# drill-rev-1.net
KiCad netlist of a schematic drawn in EAGLE
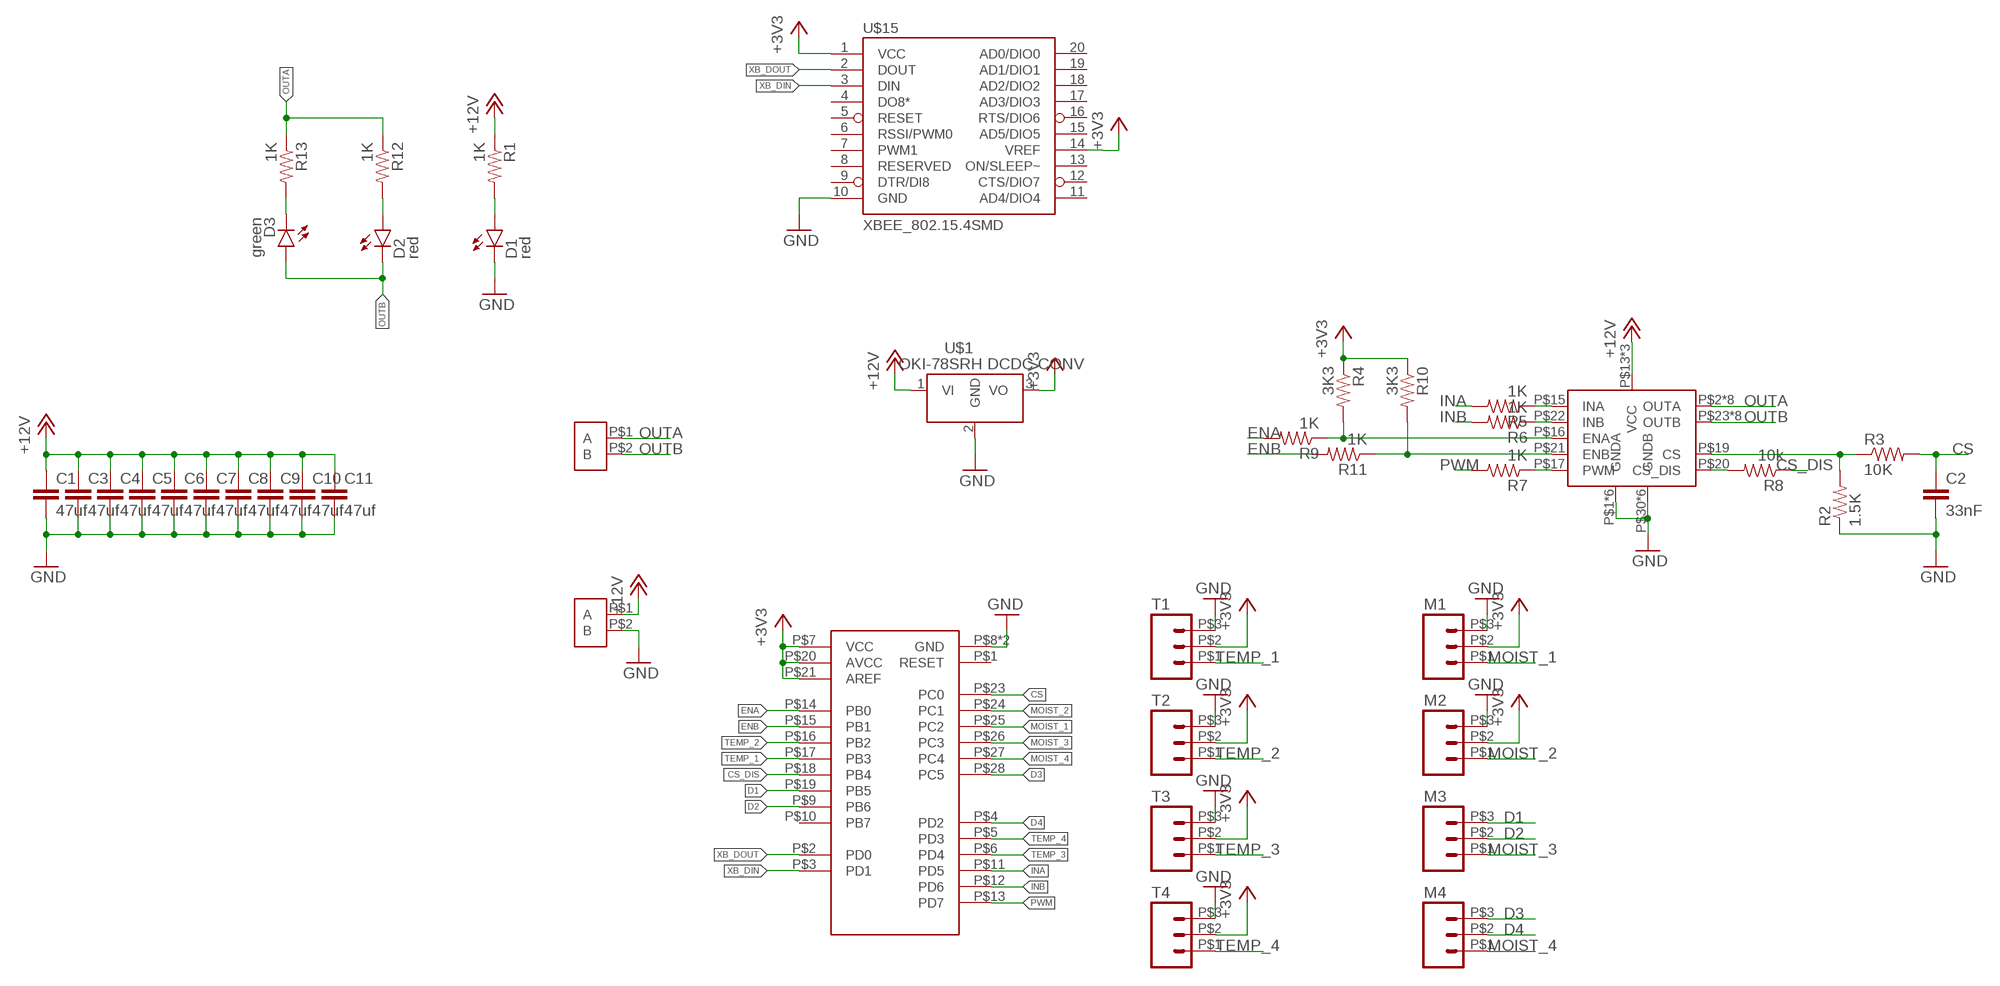
[diagram p0: schematic, sheet 1]

(export (version "E")
  (design (tool "Eeschema 10.0.6"))
  (components
    (comp (ref "C1")
      (value "47uf")
      (footprint "eagle-import:1210")
      (libsource (lib "eagle-import") (part "CAP1210"))
    )
    (comp (ref "C2")
      (value "33nF")
      (footprint "eagle-import:0603-CAP")
      (libsource (lib "eagle-import") (part "CAP0603-CAP"))
    )
    (comp (ref "C3")
      (value "47uf")
      (footprint "eagle-import:1210")
      (libsource (lib "eagle-import") (part "CAP1210"))
    )
    (comp (ref "C4")
      (value "47uf")
      (footprint "eagle-import:1210")
      (libsource (lib "eagle-import") (part "CAP1210"))
    )
    (comp (ref "C5")
      (value "47uf")
      (footprint "eagle-import:1210")
      (libsource (lib "eagle-import") (part "CAP1210"))
    )
    (comp (ref "C6")
      (value "47uf")
      (footprint "eagle-import:1210")
      (libsource (lib "eagle-import") (part "CAP1210"))
    )
    (comp (ref "C7")
      (value "47uf")
      (footprint "eagle-import:1210")
      (libsource (lib "eagle-import") (part "CAP1210"))
    )
    (comp (ref "C8")
      (value "47uf")
      (footprint "eagle-import:1210")
      (libsource (lib "eagle-import") (part "CAP1210"))
    )
    (comp (ref "C9")
      (value "47uf")
      (footprint "eagle-import:1210")
      (libsource (lib "eagle-import") (part "CAP1210"))
    )
    (comp (ref "C10")
      (value "47uf")
      (footprint "eagle-import:1210")
      (libsource (lib "eagle-import") (part "CAP1210"))
    )
    (comp (ref "C11")
      (value "47uf")
      (footprint "eagle-import:1210")
      (libsource (lib "eagle-import") (part "CAP1210"))
    )
    (comp (ref "D1")
      (value "red")
      (footprint "eagle-import:LED-0603")
      (libsource (lib "eagle-import") (part "LED0603"))
    )
    (comp (ref "D2")
      (value "red")
      (footprint "eagle-import:LED-0603")
      (libsource (lib "eagle-import") (part "LED0603"))
    )
    (comp (ref "D3")
      (value "green")
      (footprint "eagle-import:LED-0603")
      (libsource (lib "eagle-import") (part "LED0603"))
    )
    (comp (ref "M1")
      (value "M03VERT")
      (footprint "eagle-import:MOLEX0436500328")
      (libsource (lib "eagle-import") (part "M03VERT"))
    )
    (comp (ref "M2")
      (value "M03VERT")
      (footprint "eagle-import:MOLEX0436500328")
      (libsource (lib "eagle-import") (part "M03VERT"))
    )
    (comp (ref "M3")
      (value "M03VERT")
      (footprint "eagle-import:MOLEX0436500328")
      (libsource (lib "eagle-import") (part "M03VERT"))
    )
    (comp (ref "M4")
      (value "M03VERT")
      (footprint "eagle-import:MOLEX0436500328")
      (libsource (lib "eagle-import") (part "M03VERT"))
    )
    (comp (ref "R1")
      (value "1K")
      (footprint "eagle-import:0603-RES")
      (libsource (lib "eagle-import") (part "RESISTOR0603"))
    )
    (comp (ref "R2")
      (value "1.5K")
      (footprint "eagle-import:0603-RES")
      (libsource (lib "eagle-import") (part "RESISTOR0603"))
    )
    (comp (ref "R3")
      (value "10K")
      (footprint "eagle-import:0603-RES")
      (libsource (lib "eagle-import") (part "RESISTOR0603"))
    )
    (comp (ref "R4")
      (value "3K3")
      (footprint "eagle-import:0603-RES")
      (libsource (lib "eagle-import") (part "RESISTOR0603"))
    )
    (comp (ref "R5")
      (value "1K")
      (footprint "eagle-import:0603-RES")
      (libsource (lib "eagle-import") (part "RESISTOR0603"))
    )
    (comp (ref "R6")
      (value "1K")
      (footprint "eagle-import:0603-RES")
      (libsource (lib "eagle-import") (part "RESISTOR0603"))
    )
    (comp (ref "R7")
      (value "1K")
      (footprint "eagle-import:0603-RES")
      (libsource (lib "eagle-import") (part "RESISTOR0603"))
    )
    (comp (ref "R8")
      (value "10k")
      (footprint "eagle-import:0603-RES")
      (libsource (lib "eagle-import") (part "RESISTOR0603"))
    )
    (comp (ref "R9")
      (value "1K")
      (footprint "eagle-import:0603-RES")
      (libsource (lib "eagle-import") (part "RESISTOR0603"))
    )
    (comp (ref "R10")
      (value "3K3")
      (footprint "eagle-import:0603-RES")
      (libsource (lib "eagle-import") (part "RESISTOR0603"))
    )
    (comp (ref "R11")
      (value "1K")
      (footprint "eagle-import:0603-RES")
      (libsource (lib "eagle-import") (part "RESISTOR0603"))
    )
    (comp (ref "R12")
      (value "1K")
      (footprint "eagle-import:0603-RES")
      (libsource (lib "eagle-import") (part "RESISTOR0603"))
    )
    (comp (ref "R13")
      (value "1K")
      (footprint "eagle-import:0603-RES")
      (libsource (lib "eagle-import") (part "RESISTOR0603"))
    )
    (comp (ref "T1")
      (value "M03VERT")
      (footprint "eagle-import:MOLEX0436500328")
      (libsource (lib "eagle-import") (part "M03VERT"))
    )
    (comp (ref "T2")
      (value "M03VERT")
      (footprint "eagle-import:MOLEX0436500328")
      (libsource (lib "eagle-import") (part "M03VERT"))
    )
    (comp (ref "T3")
      (value "M03VERT")
      (footprint "eagle-import:MOLEX0436500328")
      (libsource (lib "eagle-import") (part "M03VERT"))
    )
    (comp (ref "T4")
      (value "M03VERT")
      (footprint "eagle-import:MOLEX0436500328")
      (libsource (lib "eagle-import") (part "M03VERT"))
    )
    (comp (ref "U$1")
      (value "Q_OKI-78SR")
      (footprint "eagle-import:OKI-78SR_HORIZ")
      (libsource (lib "eagle-import") (part "Q_OKI-78SR"))
    )
    (comp (ref "U$3")
      (value "TE_2POS-5MM_SCREW_TERM")
      (footprint "eagle-import:TE_2POS-5MM_SCREW_TERM")
      (libsource (lib "eagle-import") (part "TE_2POS-5MM_SCREW_TERM"))
    )
    (comp (ref "U$5")
      (value "TE_2POS-5MM_SCREW_TERM")
      (footprint "eagle-import:TE_2POS-5MM_SCREW_TERM")
      (libsource (lib "eagle-import") (part "TE_2POS-5MM_SCREW_TERM"))
    )
    (comp (ref "U$6")
      (value "VNH5XXX_HBRIDGEVNH5050A")
      (footprint "eagle-import:POWERSSO-36_TP")
      (libsource (lib "eagle-import") (part "VNH5XXX_HBRIDGEVNH5050A"))
    )
    (comp (ref "U$13")
      (value "DIP_SKT_ATMEGA")
      (footprint "eagle-import:DIP_SKT_ATMEGA")
      (libsource (lib "eagle-import") (part "DIP_SKT_ATMEGA"))
    )
    (comp (ref "U$15")
      (value "XBEE_802.15.4SMD")
      (footprint "eagle-import:XBEE_802.15.4_SMD")
      (libsource (lib "eagle-import") (part "XBEE_802.15.4SMD"))
    )
  )
  (nets
    (net (code "1") (name "+3V3") (class "Default")
      (node (ref "M1") (pin "P$2") (pinfunction "2_P$2") (pintype "passive"))
      (node (ref "M2") (pin "P$2") (pinfunction "2_P$2") (pintype "passive"))
      (node (ref "R10") (pin "1") (pinfunction "1_1") (pintype "passive"))
      (node (ref "R4") (pin "1") (pinfunction "1_1") (pintype "passive"))
      (node (ref "T1") (pin "P$2") (pinfunction "2_P$2") (pintype "passive"))
      (node (ref "T2") (pin "P$2") (pinfunction "2_P$2") (pintype "passive"))
      (node (ref "T3") (pin "P$2") (pinfunction "2_P$2") (pintype "passive"))
      (node (ref "T4") (pin "P$2") (pinfunction "2_P$2") (pintype "passive"))
      (node (ref "U$1") (pin "3") (pinfunction "VO_3") (pintype "bidirectional"))
      (node (ref "U$13") (pin "P$20") (pinfunction "AVCC_P$20") (pintype "bidirectional"))
      (node (ref "U$13") (pin "P$21") (pinfunction "AREF_P$21") (pintype "bidirectional"))
      (node (ref "U$13") (pin "P$7") (pinfunction "VCC_P$7") (pintype "bidirectional"))
      (node (ref "U$15") (pin "1") (pinfunction "VCC_1") (pintype "power_in"))
      (node (ref "U$15") (pin "14") (pinfunction "VREF_14") (pintype "bidirectional"))
    )
    (net (code "2") (name "+12V") (class "Default")
      (node (ref "C1") (pin "1") (pinfunction "1_1") (pintype "passive"))
      (node (ref "C10") (pin "1") (pinfunction "1_1") (pintype "passive"))
      (node (ref "C11") (pin "1") (pinfunction "1_1") (pintype "passive"))
      (node (ref "C3") (pin "1") (pinfunction "1_1") (pintype "passive"))
      (node (ref "C4") (pin "1") (pinfunction "1_1") (pintype "passive"))
      (node (ref "C5") (pin "1") (pinfunction "1_1") (pintype "passive"))
      (node (ref "C6") (pin "1") (pinfunction "1_1") (pintype "passive"))
      (node (ref "C7") (pin "1") (pinfunction "1_1") (pintype "passive"))
      (node (ref "C8") (pin "1") (pinfunction "1_1") (pintype "passive"))
      (node (ref "C9") (pin "1") (pinfunction "1_1") (pintype "passive"))
      (node (ref "R1") (pin "1") (pinfunction "1_1") (pintype "passive"))
      (node (ref "U$1") (pin "1") (pinfunction "VI_1") (pintype "bidirectional"))
      (node (ref "U$5") (pin "P$1") (pinfunction "A_P$1") (pintype "bidirectional"))
      (node (ref "U$6") (pin "P$13") (pinfunction "VCC_P$13") (pintype "bidirectional"))
      (node (ref "U$6") (pin "P$24") (pinfunction "VCC_P$24") (pintype "bidirectional"))
      (node (ref "U$6") (pin "SLUG1") (pinfunction "VCC_SLUG1") (pintype "bidirectional"))
    )
    (net (code "3") (name "CS") (class "Default")
      (node (ref "C2") (pin "1") (pinfunction "1_1") (pintype "passive"))
      (node (ref "R3") (pin "2") (pinfunction "2_2") (pintype "passive"))
      (node (ref "U$13") (pin "P$23") (pinfunction "PC0_P$23") (pintype "bidirectional"))
    )
    (net (code "4") (name "CS_DIS") (class "Default")
      (node (ref "R8") (pin "1") (pinfunction "1_1") (pintype "passive"))
      (node (ref "U$13") (pin "P$18") (pinfunction "PB4_P$18") (pintype "bidirectional"))
    )
    (net (code "5") (name "D1") (class "Default")
      (node (ref "M3") (pin "P$3") (pinfunction "3_P$3") (pintype "passive"))
      (node (ref "U$13") (pin "P$19") (pinfunction "PB5_P$19") (pintype "bidirectional"))
    )
    (net (code "6") (name "D2") (class "Default")
      (node (ref "M3") (pin "P$2") (pinfunction "2_P$2") (pintype "passive"))
      (node (ref "U$13") (pin "P$9") (pinfunction "PB6_P$9") (pintype "bidirectional"))
    )
    (net (code "7") (name "D3") (class "Default")
      (node (ref "M4") (pin "P$3") (pinfunction "3_P$3") (pintype "passive"))
      (node (ref "U$13") (pin "P$28") (pinfunction "PC5_P$28") (pintype "bidirectional"))
    )
    (net (code "8") (name "D4") (class "Default")
      (node (ref "M4") (pin "P$2") (pinfunction "2_P$2") (pintype "passive"))
      (node (ref "U$13") (pin "P$4") (pinfunction "PD2_P$4") (pintype "bidirectional"))
    )
    (net (code "9") (name "ENA") (class "Default")
      (node (ref "R9") (pin "2") (pinfunction "2_2") (pintype "passive"))
      (node (ref "U$13") (pin "P$14") (pinfunction "PB0_P$14") (pintype "bidirectional"))
    )
    (net (code "10") (name "ENB") (class "Default")
      (node (ref "R11") (pin "2") (pinfunction "2_2") (pintype "passive"))
      (node (ref "U$13") (pin "P$15") (pinfunction "PB1_P$15") (pintype "bidirectional"))
    )
    (net (code "11") (name "GND") (class "Default")
      (node (ref "C1") (pin "2") (pinfunction "2_2") (pintype "passive"))
      (node (ref "C10") (pin "2") (pinfunction "2_2") (pintype "passive"))
      (node (ref "C11") (pin "2") (pinfunction "2_2") (pintype "passive"))
      (node (ref "C2") (pin "2") (pinfunction "2_2") (pintype "passive"))
      (node (ref "C3") (pin "2") (pinfunction "2_2") (pintype "passive"))
      (node (ref "C4") (pin "2") (pinfunction "2_2") (pintype "passive"))
      (node (ref "C5") (pin "2") (pinfunction "2_2") (pintype "passive"))
      (node (ref "C6") (pin "2") (pinfunction "2_2") (pintype "passive"))
      (node (ref "C7") (pin "2") (pinfunction "2_2") (pintype "passive"))
      (node (ref "C8") (pin "2") (pinfunction "2_2") (pintype "passive"))
      (node (ref "C9") (pin "2") (pinfunction "2_2") (pintype "passive"))
      (node (ref "D1") (pin "C") (pinfunction "C_C") (pintype "passive"))
      (node (ref "M1") (pin "P$3") (pinfunction "3_P$3") (pintype "passive"))
      (node (ref "M2") (pin "P$3") (pinfunction "3_P$3") (pintype "passive"))
      (node (ref "R2") (pin "1") (pinfunction "1_1") (pintype "passive"))
      (node (ref "T1") (pin "P$3") (pinfunction "3_P$3") (pintype "passive"))
      (node (ref "T2") (pin "P$3") (pinfunction "3_P$3") (pintype "passive"))
      (node (ref "T3") (pin "P$3") (pinfunction "3_P$3") (pintype "passive"))
      (node (ref "T4") (pin "P$3") (pinfunction "3_P$3") (pintype "passive"))
      (node (ref "U$1") (pin "2") (pinfunction "GND_2") (pintype "bidirectional"))
      (node (ref "U$13") (pin "P$22") (pinfunction "GND_P$22") (pintype "bidirectional"))
      (node (ref "U$13") (pin "P$8") (pinfunction "GND_P$8") (pintype "bidirectional"))
      (node (ref "U$15") (pin "10") (pinfunction "GND_10") (pintype "power_in"))
      (node (ref "U$5") (pin "P$2") (pinfunction "B_P$2") (pintype "bidirectional"))
      (node (ref "U$6") (pin "P$1") (pinfunction "GNDA_P$1") (pintype "bidirectional"))
      (node (ref "U$6") (pin "P$3") (pinfunction "GNDA_P$3") (pintype "bidirectional"))
      (node (ref "U$6") (pin "P$30") (pinfunction "GNDB_P$30") (pintype "bidirectional"))
      (node (ref "U$6") (pin "P$31") (pinfunction "GNDB_P$31") (pintype "bidirectional"))
      (node (ref "U$6") (pin "P$32") (pinfunction "GNDB_P$32") (pintype "bidirectional"))
      (node (ref "U$6") (pin "P$33") (pinfunction "GNDB_P$33") (pintype "bidirectional"))
      (node (ref "U$6") (pin "P$34") (pinfunction "GNDB_P$34") (pintype "bidirectional"))
      (node (ref "U$6") (pin "P$36") (pinfunction "GNDB_P$36") (pintype "bidirectional"))
      (node (ref "U$6") (pin "P$4") (pinfunction "GNDA_P$4") (pintype "bidirectional"))
      (node (ref "U$6") (pin "P$5") (pinfunction "GNDA_P$5") (pintype "bidirectional"))
      (node (ref "U$6") (pin "P$6") (pinfunction "GNDA_P$6") (pintype "bidirectional"))
      (node (ref "U$6") (pin "P$7") (pinfunction "GNDA_P$7") (pintype "bidirectional"))
    )
    (net (code "12") (name "INA") (class "Default")
      (node (ref "R5") (pin "2") (pinfunction "2_2") (pintype "passive"))
      (node (ref "U$13") (pin "P$11") (pinfunction "PD5_P$11") (pintype "bidirectional"))
    )
    (net (code "13") (name "INB") (class "Default")
      (node (ref "R6") (pin "2") (pinfunction "2_2") (pintype "passive"))
      (node (ref "U$13") (pin "P$12") (pinfunction "PD6_P$12") (pintype "bidirectional"))
    )
    (net (code "14") (name "MOIST_1") (class "Default")
      (node (ref "M1") (pin "P$1") (pinfunction "1_P$1") (pintype "passive"))
      (node (ref "U$13") (pin "P$25") (pinfunction "PC2_P$25") (pintype "bidirectional"))
    )
    (net (code "15") (name "MOIST_2") (class "Default")
      (node (ref "M2") (pin "P$1") (pinfunction "1_P$1") (pintype "passive"))
      (node (ref "U$13") (pin "P$24") (pinfunction "PC1_P$24") (pintype "bidirectional"))
    )
    (net (code "16") (name "MOIST_3") (class "Default")
      (node (ref "M3") (pin "P$1") (pinfunction "1_P$1") (pintype "passive"))
      (node (ref "U$13") (pin "P$26") (pinfunction "PC3_P$26") (pintype "bidirectional"))
    )
    (net (code "17") (name "MOIST_4") (class "Default")
      (node (ref "M4") (pin "P$1") (pinfunction "1_P$1") (pintype "passive"))
      (node (ref "U$13") (pin "P$27") (pinfunction "PC4_P$27") (pintype "bidirectional"))
    )
    (net (code "18") (name "Net-(D1-PadA)") (class "Default")
      (node (ref "D1") (pin "A") (pinfunction "A_A") (pintype "passive"))
      (node (ref "R1") (pin "2") (pinfunction "2_2") (pintype "passive"))
    )
    (net (code "19") (name "Net-(D2-PadA)") (class "Default")
      (node (ref "D2") (pin "A") (pinfunction "A_A") (pintype "passive"))
      (node (ref "R12") (pin "2") (pinfunction "2_2") (pintype "passive"))
    )
    (net (code "20") (name "Net-(D3-PadC)") (class "Default")
      (node (ref "D3") (pin "C") (pinfunction "C_C") (pintype "passive"))
      (node (ref "R13") (pin "2") (pinfunction "2_2") (pintype "passive"))
    )
    (net (code "21") (name "Net-(U$6-CS)") (class "Default")
      (node (ref "R2") (pin "2") (pinfunction "2_2") (pintype "passive"))
      (node (ref "R3") (pin "1") (pinfunction "1_1") (pintype "passive"))
      (node (ref "U$6") (pin "P$19") (pinfunction "CS_P$19") (pintype "bidirectional"))
    )
    (net (code "22") (name "Net-(U$6-CS_DIS)") (class "Default")
      (node (ref "R8") (pin "2") (pinfunction "2_2") (pintype "passive"))
      (node (ref "U$6") (pin "P$20") (pinfunction "CS_DIS_P$20") (pintype "bidirectional"))
    )
    (net (code "23") (name "Net-(U$6-ENA)") (class "Default")
      (node (ref "R4") (pin "2") (pinfunction "2_2") (pintype "passive"))
      (node (ref "R9") (pin "1") (pinfunction "1_1") (pintype "passive"))
      (node (ref "U$6") (pin "P$16") (pinfunction "ENA_P$16") (pintype "bidirectional"))
    )
    (net (code "24") (name "Net-(U$6-ENB)") (class "Default")
      (node (ref "R10") (pin "2") (pinfunction "2_2") (pintype "passive"))
      (node (ref "R11") (pin "1") (pinfunction "1_1") (pintype "passive"))
      (node (ref "U$6") (pin "P$21") (pinfunction "ENB_P$21") (pintype "bidirectional"))
    )
    (net (code "25") (name "Net-(U$6-INA)") (class "Default")
      (node (ref "R5") (pin "1") (pinfunction "1_1") (pintype "passive"))
      (node (ref "U$6") (pin "P$15") (pinfunction "INA_P$15") (pintype "bidirectional"))
    )
    (net (code "26") (name "Net-(U$6-INB)") (class "Default")
      (node (ref "R6") (pin "1") (pinfunction "1_1") (pintype "passive"))
      (node (ref "U$6") (pin "P$22") (pinfunction "INB_P$22") (pintype "bidirectional"))
    )
    (net (code "27") (name "Net-(U$6-PWM)") (class "Default")
      (node (ref "R7") (pin "1") (pinfunction "1_1") (pintype "passive"))
      (node (ref "U$6") (pin "P$17") (pinfunction "PWM_P$17") (pintype "bidirectional"))
    )
    (net (code "28") (name "OUTA") (class "Default")
      (node (ref "R12") (pin "1") (pinfunction "1_1") (pintype "passive"))
      (node (ref "R13") (pin "1") (pinfunction "1_1") (pintype "passive"))
      (node (ref "U$3") (pin "P$1") (pinfunction "A_P$1") (pintype "bidirectional"))
      (node (ref "U$6") (pin "P$10") (pinfunction "OUTA_P$10") (pintype "bidirectional"))
      (node (ref "U$6") (pin "P$11") (pinfunction "OUTA_P$11") (pintype "bidirectional"))
      (node (ref "U$6") (pin "P$12") (pinfunction "OUTA_P$12") (pintype "bidirectional"))
      (node (ref "U$6") (pin "P$14") (pinfunction "OUTA_P$14") (pintype "bidirectional"))
      (node (ref "U$6") (pin "P$2") (pinfunction "OUTA_P$2") (pintype "bidirectional"))
      (node (ref "U$6") (pin "P$8") (pinfunction "OUTA_P$8") (pintype "bidirectional"))
      (node (ref "U$6") (pin "P$9") (pinfunction "OUTA_P$9") (pintype "bidirectional"))
      (node (ref "U$6") (pin "SLUG2") (pinfunction "OUTA_SLUG2") (pintype "bidirectional"))
    )
    (net (code "29") (name "OUTB") (class "Default")
      (node (ref "D2") (pin "C") (pinfunction "C_C") (pintype "passive"))
      (node (ref "D3") (pin "A") (pinfunction "A_A") (pintype "passive"))
      (node (ref "U$3") (pin "P$2") (pinfunction "B_P$2") (pintype "bidirectional"))
      (node (ref "U$6") (pin "P$23") (pinfunction "OUTB_P$23") (pintype "bidirectional"))
      (node (ref "U$6") (pin "P$25") (pinfunction "OUTB_P$25") (pintype "bidirectional"))
      (node (ref "U$6") (pin "P$26") (pinfunction "OUTB_P$26") (pintype "bidirectional"))
      (node (ref "U$6") (pin "P$27") (pinfunction "OUTB_P$27") (pintype "bidirectional"))
      (node (ref "U$6") (pin "P$28") (pinfunction "OUTB_P$28") (pintype "bidirectional"))
      (node (ref "U$6") (pin "P$29") (pinfunction "OUTB_P$29") (pintype "bidirectional"))
      (node (ref "U$6") (pin "P$35") (pinfunction "OUTB_P$35") (pintype "bidirectional"))
      (node (ref "U$6") (pin "SLUG3") (pinfunction "OUTB_SLUG3") (pintype "bidirectional"))
    )
    (net (code "30") (name "PWM") (class "Default")
      (node (ref "R7") (pin "2") (pinfunction "2_2") (pintype "passive"))
      (node (ref "U$13") (pin "P$13") (pinfunction "PD7_P$13") (pintype "bidirectional"))
    )
    (net (code "31") (name "TEMP_1") (class "Default")
      (node (ref "T1") (pin "P$1") (pinfunction "1_P$1") (pintype "passive"))
      (node (ref "U$13") (pin "P$17") (pinfunction "PB3_P$17") (pintype "bidirectional"))
    )
    (net (code "32") (name "TEMP_2") (class "Default")
      (node (ref "T2") (pin "P$1") (pinfunction "1_P$1") (pintype "passive"))
      (node (ref "U$13") (pin "P$16") (pinfunction "PB2_P$16") (pintype "bidirectional"))
    )
    (net (code "33") (name "TEMP_3") (class "Default")
      (node (ref "T3") (pin "P$1") (pinfunction "1_P$1") (pintype "passive"))
      (node (ref "U$13") (pin "P$6") (pinfunction "PD4_P$6") (pintype "bidirectional"))
    )
    (net (code "34") (name "TEMP_4") (class "Default")
      (node (ref "T4") (pin "P$1") (pinfunction "1_P$1") (pintype "passive"))
      (node (ref "U$13") (pin "P$5") (pinfunction "PD3_P$5") (pintype "bidirectional"))
    )
    (net (code "35") (name "XB_DIN") (class "Default")
      (node (ref "U$13") (pin "P$3") (pinfunction "PD1_P$3") (pintype "bidirectional"))
      (node (ref "U$15") (pin "3") (pinfunction "DIN_3") (pintype "input"))
    )
    (net (code "36") (name "XB_DOUT") (class "Default")
      (node (ref "U$13") (pin "P$2") (pinfunction "PD0_P$2") (pintype "bidirectional"))
      (node (ref "U$15") (pin "2") (pinfunction "DOUT_2") (pintype "output"))
    )
    (net (code "37") (name "unconnected-(U$13-PB7-PadP$10)") (class "Default")
      (node (ref "U$13") (pin "P$10") (pinfunction "PB7_P$10") (pintype "bidirectional"))
    )
    (net (code "38") (name "unconnected-(U$13-RESET-PadP$1)") (class "Default")
      (node (ref "U$13") (pin "P$1") (pinfunction "RESET_P$1") (pintype "bidirectional"))
    )
    (net (code "39") (name "unconnected-(U$15-AD0{slash}DIO0-Pad20)") (class "Default")
      (node (ref "U$15") (pin "20") (pinfunction "AD0/DIO0_20") (pintype "bidirectional"))
    )
    (net (code "40") (name "unconnected-(U$15-AD1{slash}DIO1-Pad19)") (class "Default")
      (node (ref "U$15") (pin "19") (pinfunction "AD1/DIO1_19") (pintype "bidirectional"))
    )
    (net (code "41") (name "unconnected-(U$15-AD2{slash}DIO2-Pad18)") (class "Default")
      (node (ref "U$15") (pin "18") (pinfunction "AD2/DIO2_18") (pintype "bidirectional"))
    )
    (net (code "42") (name "unconnected-(U$15-AD3{slash}DIO3-Pad17)") (class "Default")
      (node (ref "U$15") (pin "17") (pinfunction "AD3/DIO3_17") (pintype "bidirectional"))
    )
    (net (code "43") (name "unconnected-(U$15-AD4{slash}DIO4-Pad11)") (class "Default")
      (node (ref "U$15") (pin "11") (pinfunction "AD4/DIO4_11") (pintype "bidirectional"))
    )
    (net (code "44") (name "unconnected-(U$15-AD5{slash}DIO5-Pad15)") (class "Default")
      (node (ref "U$15") (pin "15") (pinfunction "AD5/DIO5_15") (pintype "bidirectional"))
    )
    (net (code "45") (name "unconnected-(U$15-CTS{slash}DIO7-Pad12)") (class "Default")
      (node (ref "U$15") (pin "12") (pinfunction "CTS/DIO7_12") (pintype "output"))
    )
    (net (code "46") (name "unconnected-(U$15-DO8*-Pad4)") (class "Default")
      (node (ref "U$15") (pin "4") (pinfunction "DO8*_4") (pintype "bidirectional"))
    )
    (net (code "47") (name "unconnected-(U$15-DTR{slash}DI8-Pad9)") (class "Default")
      (node (ref "U$15") (pin "9") (pinfunction "DTR/DI8_9") (pintype "bidirectional"))
    )
    (net (code "48") (name "unconnected-(U$15-ON{slash}SLEEP~{}-Pad13)") (class "Default")
      (node (ref "U$15") (pin "13") (pinfunction "ON/SLEEP~{}_13") (pintype "bidirectional"))
    )
    (net (code "49") (name "unconnected-(U$15-PWM1-Pad7)") (class "Default")
      (node (ref "U$15") (pin "7") (pinfunction "PWM1_7") (pintype "bidirectional"))
    )
    (net (code "50") (name "unconnected-(U$15-RESERVED-Pad8)") (class "Default")
      (node (ref "U$15") (pin "8") (pinfunction "RESERVED_8") (pintype "bidirectional"))
    )
    (net (code "51") (name "unconnected-(U$15-RESET-Pad5)") (class "Default")
      (node (ref "U$15") (pin "5") (pinfunction "RESET_5") (pintype "input"))
    )
    (net (code "52") (name "unconnected-(U$15-RSSI{slash}PWM0-Pad6)") (class "Default")
      (node (ref "U$15") (pin "6") (pinfunction "RSSI/PWM0_6") (pintype "bidirectional"))
    )
    (net (code "53") (name "unconnected-(U$15-RTS{slash}DIO6-Pad16)") (class "Default")
      (node (ref "U$15") (pin "16") (pinfunction "RTS/DIO6_16") (pintype "input"))
    )
  )
)
